# Ext_connectors.net
KiCad netlist of a schematic drawn in Altium Designer
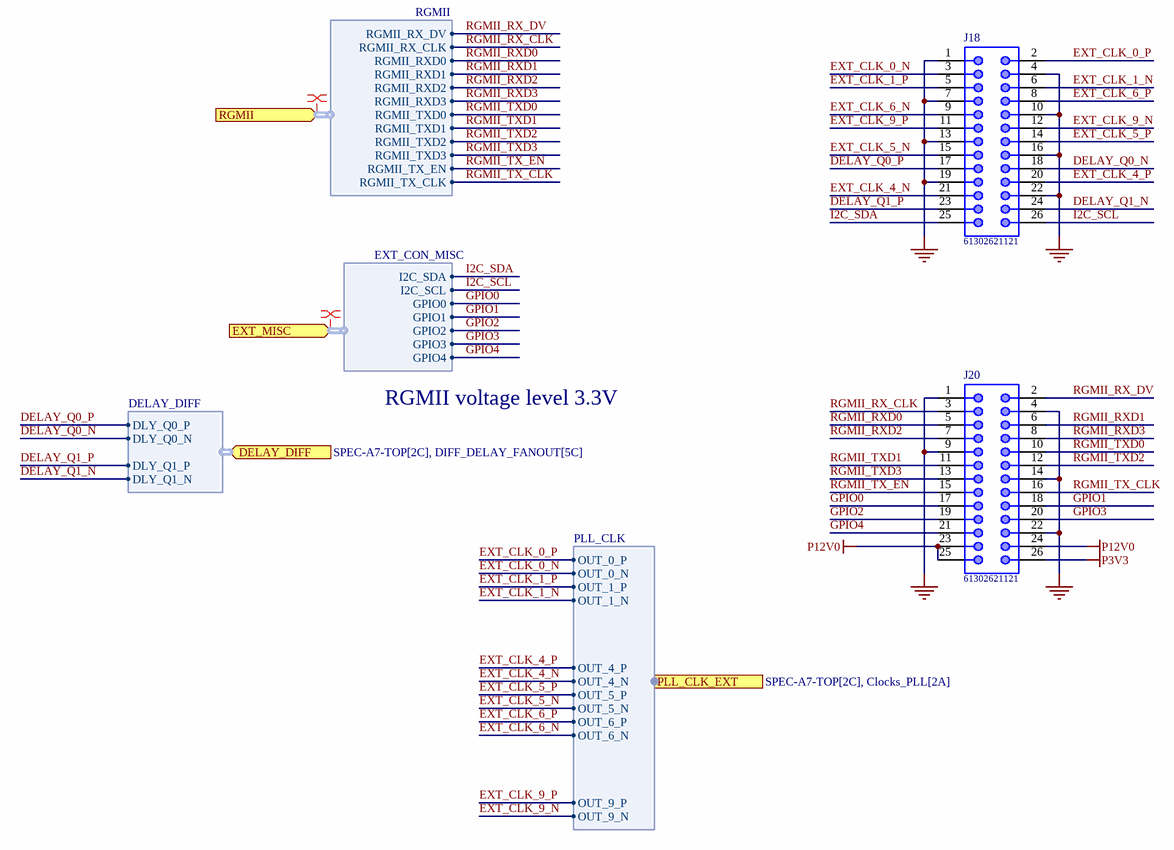
[diagram p0: Ext_connectors.SchDoc]

(export (version "E")
  (design (tool "Eeschema 10.0.6"))
  (components
    (comp (ref "J18")
      (value "61302621121")
      (footprint "61302621121")
      (description "WR-PHD Pin Header, THT, pitch 2.54mm, Dual Row, Vertical, 26pin")
      (fields (field (name "PUBLISHER") "Wurth Elektronik"))
      (libsource (lib "ALTIUM-WR-PHD_PIN_HEADER_SOCKET_HEADER-rev19a") (part "61302621121"))
    )
    (comp (ref "J20")
      (value "61302621121")
      (footprint "61302621121")
      (description "WR-PHD Pin Header, THT, pitch 2.54mm, Dual Row, Vertical, 26pin")
      (fields (field (name "PUBLISHER") "Wurth Elektronik"))
      (libsource (lib "ALTIUM-WR-PHD_PIN_HEADER_SOCKET_HEADER-rev19a") (part "61302621121"))
    )
  )
  (nets
    (net (code "5") (name "/DELAY_Q0_N") (class "Default")
      (node (ref "J18") (pin "18") (pinfunction "18_18") (pintype "passive"))
    )
    (net (code "6") (name "/DELAY_Q0_P") (class "Default")
      (node (ref "J18") (pin "17") (pinfunction "17_17") (pintype "passive"))
    )
    (net (code "7") (name "/DELAY_Q1_N") (class "Default")
      (node (ref "J18") (pin "24") (pinfunction "24_24") (pintype "passive"))
    )
    (net (code "8") (name "/DELAY_Q1_P") (class "Default")
      (node (ref "J18") (pin "23") (pinfunction "23_23") (pintype "passive"))
    )
    (net (code "9") (name "/EXT_CLK_0_N") (class "Default")
      (node (ref "J18") (pin "3") (pinfunction "3_3") (pintype "passive"))
    )
    (net (code "10") (name "/EXT_CLK_0_P") (class "Default")
      (node (ref "J18") (pin "2") (pinfunction "2_2") (pintype "passive"))
    )
    (net (code "11") (name "/EXT_CLK_1_N") (class "Default")
      (node (ref "J18") (pin "6") (pinfunction "6_6") (pintype "passive"))
    )
    (net (code "12") (name "/EXT_CLK_1_P") (class "Default")
      (node (ref "J18") (pin "5") (pinfunction "5_5") (pintype "passive"))
    )
    (net (code "13") (name "/EXT_CLK_4_N") (class "Default")
      (node (ref "J18") (pin "21") (pinfunction "21_21") (pintype "passive"))
    )
    (net (code "14") (name "/EXT_CLK_4_P") (class "Default")
      (node (ref "J18") (pin "20") (pinfunction "20_20") (pintype "passive"))
    )
    (net (code "15") (name "/EXT_CLK_5_N") (class "Default")
      (node (ref "J18") (pin "15") (pinfunction "15_15") (pintype "passive"))
    )
    (net (code "16") (name "/EXT_CLK_5_P") (class "Default")
      (node (ref "J18") (pin "14") (pinfunction "14_14") (pintype "passive"))
    )
    (net (code "17") (name "/EXT_CLK_6_N") (class "Default")
      (node (ref "J18") (pin "9") (pinfunction "9_9") (pintype "passive"))
    )
    (net (code "18") (name "/EXT_CLK_6_P") (class "Default")
      (node (ref "J18") (pin "8") (pinfunction "8_8") (pintype "passive"))
    )
    (net (code "19") (name "/EXT_CLK_9_N") (class "Default")
      (node (ref "J18") (pin "12") (pinfunction "12_12") (pintype "passive"))
    )
    (net (code "20") (name "/EXT_CLK_9_P") (class "Default")
      (node (ref "J18") (pin "11") (pinfunction "11_11") (pintype "passive"))
    )
    (net (code "21") (name "/GPIO0") (class "Default")
      (node (ref "J20") (pin "17") (pinfunction "17_17") (pintype "passive"))
    )
    (net (code "22") (name "/GPIO1") (class "Default")
      (node (ref "J20") (pin "18") (pinfunction "18_18") (pintype "passive"))
    )
    (net (code "23") (name "/GPIO2") (class "Default")
      (node (ref "J20") (pin "19") (pinfunction "19_19") (pintype "passive"))
    )
    (net (code "24") (name "/GPIO3") (class "Default")
      (node (ref "J20") (pin "20") (pinfunction "20_20") (pintype "passive"))
    )
    (net (code "25") (name "/GPIO4") (class "Default")
      (node (ref "J20") (pin "21") (pinfunction "21_21") (pintype "passive"))
    )
    (net (code "26") (name "/I2C_SCL") (class "Default")
      (node (ref "J18") (pin "26") (pinfunction "26_26") (pintype "passive"))
    )
    (net (code "27") (name "/I2C_SDA") (class "Default")
      (node (ref "J18") (pin "25") (pinfunction "25_25") (pintype "passive"))
    )
    (net (code "28") (name "/RGMII_RXD0") (class "Default")
      (node (ref "J20") (pin "5") (pinfunction "5_5") (pintype "passive"))
    )
    (net (code "29") (name "/RGMII_RXD1") (class "Default")
      (node (ref "J20") (pin "6") (pinfunction "6_6") (pintype "passive"))
    )
    (net (code "30") (name "/RGMII_RXD2") (class "Default")
      (node (ref "J20") (pin "7") (pinfunction "7_7") (pintype "passive"))
    )
    (net (code "31") (name "/RGMII_RXD3") (class "Default")
      (node (ref "J20") (pin "8") (pinfunction "8_8") (pintype "passive"))
    )
    (net (code "32") (name "/RGMII_RX_CLK") (class "Default")
      (node (ref "J20") (pin "3") (pinfunction "3_3") (pintype "passive"))
    )
    (net (code "33") (name "/RGMII_RX_DV") (class "Default")
      (node (ref "J20") (pin "2") (pinfunction "2_2") (pintype "passive"))
    )
    (net (code "34") (name "/RGMII_TXD0") (class "Default")
      (node (ref "J20") (pin "10") (pinfunction "10_10") (pintype "passive"))
    )
    (net (code "35") (name "/RGMII_TXD1") (class "Default")
      (node (ref "J20") (pin "11") (pinfunction "11_11") (pintype "passive"))
    )
    (net (code "36") (name "/RGMII_TXD2") (class "Default")
      (node (ref "J20") (pin "12") (pinfunction "12_12") (pintype "passive"))
    )
    (net (code "37") (name "/RGMII_TXD3") (class "Default")
      (node (ref "J20") (pin "13") (pinfunction "13_13") (pintype "passive"))
    )
    (net (code "38") (name "/RGMII_TX_CLK") (class "Default")
      (node (ref "J20") (pin "16") (pinfunction "16_16") (pintype "passive"))
    )
    (net (code "39") (name "/RGMII_TX_EN") (class "Default")
      (node (ref "J20") (pin "15") (pinfunction "15_15") (pintype "passive"))
    )
    (net (code "44") (name "GND") (class "Default")
      (node (ref "J18") (pin "1") (pinfunction "1_1") (pintype "passive"))
      (node (ref "J18") (pin "10") (pinfunction "10_10") (pintype "passive"))
      (node (ref "J18") (pin "13") (pinfunction "13_13") (pintype "passive"))
      (node (ref "J18") (pin "16") (pinfunction "16_16") (pintype "passive"))
      (node (ref "J18") (pin "19") (pinfunction "19_19") (pintype "passive"))
      (node (ref "J18") (pin "22") (pinfunction "22_22") (pintype "passive"))
      (node (ref "J18") (pin "4") (pinfunction "4_4") (pintype "passive"))
      (node (ref "J18") (pin "7") (pinfunction "7_7") (pintype "passive"))
      (node (ref "J20") (pin "1") (pinfunction "1_1") (pintype "passive"))
      (node (ref "J20") (pin "14") (pinfunction "14_14") (pintype "passive"))
      (node (ref "J20") (pin "22") (pinfunction "22_22") (pintype "passive"))
      (node (ref "J20") (pin "4") (pinfunction "4_4") (pintype "passive"))
      (node (ref "J20") (pin "9") (pinfunction "9_9") (pintype "passive"))
    )
    (net (code "45") (name "P3V3") (class "Default")
      (node (ref "J20") (pin "26") (pinfunction "26_26") (pintype "passive"))
    )
    (net (code "46") (name "P12V0") (class "Default")
      (node (ref "J20") (pin "23") (pinfunction "23_23") (pintype "passive"))
      (node (ref "J20") (pin "24") (pinfunction "24_24") (pintype "passive"))
      (node (ref "J20") (pin "25") (pinfunction "25_25") (pintype "passive"))
    )
  )
)
